# HIVE_BOARD_USB.net
KiCad netlist of a schematic drawn in Altium Designer
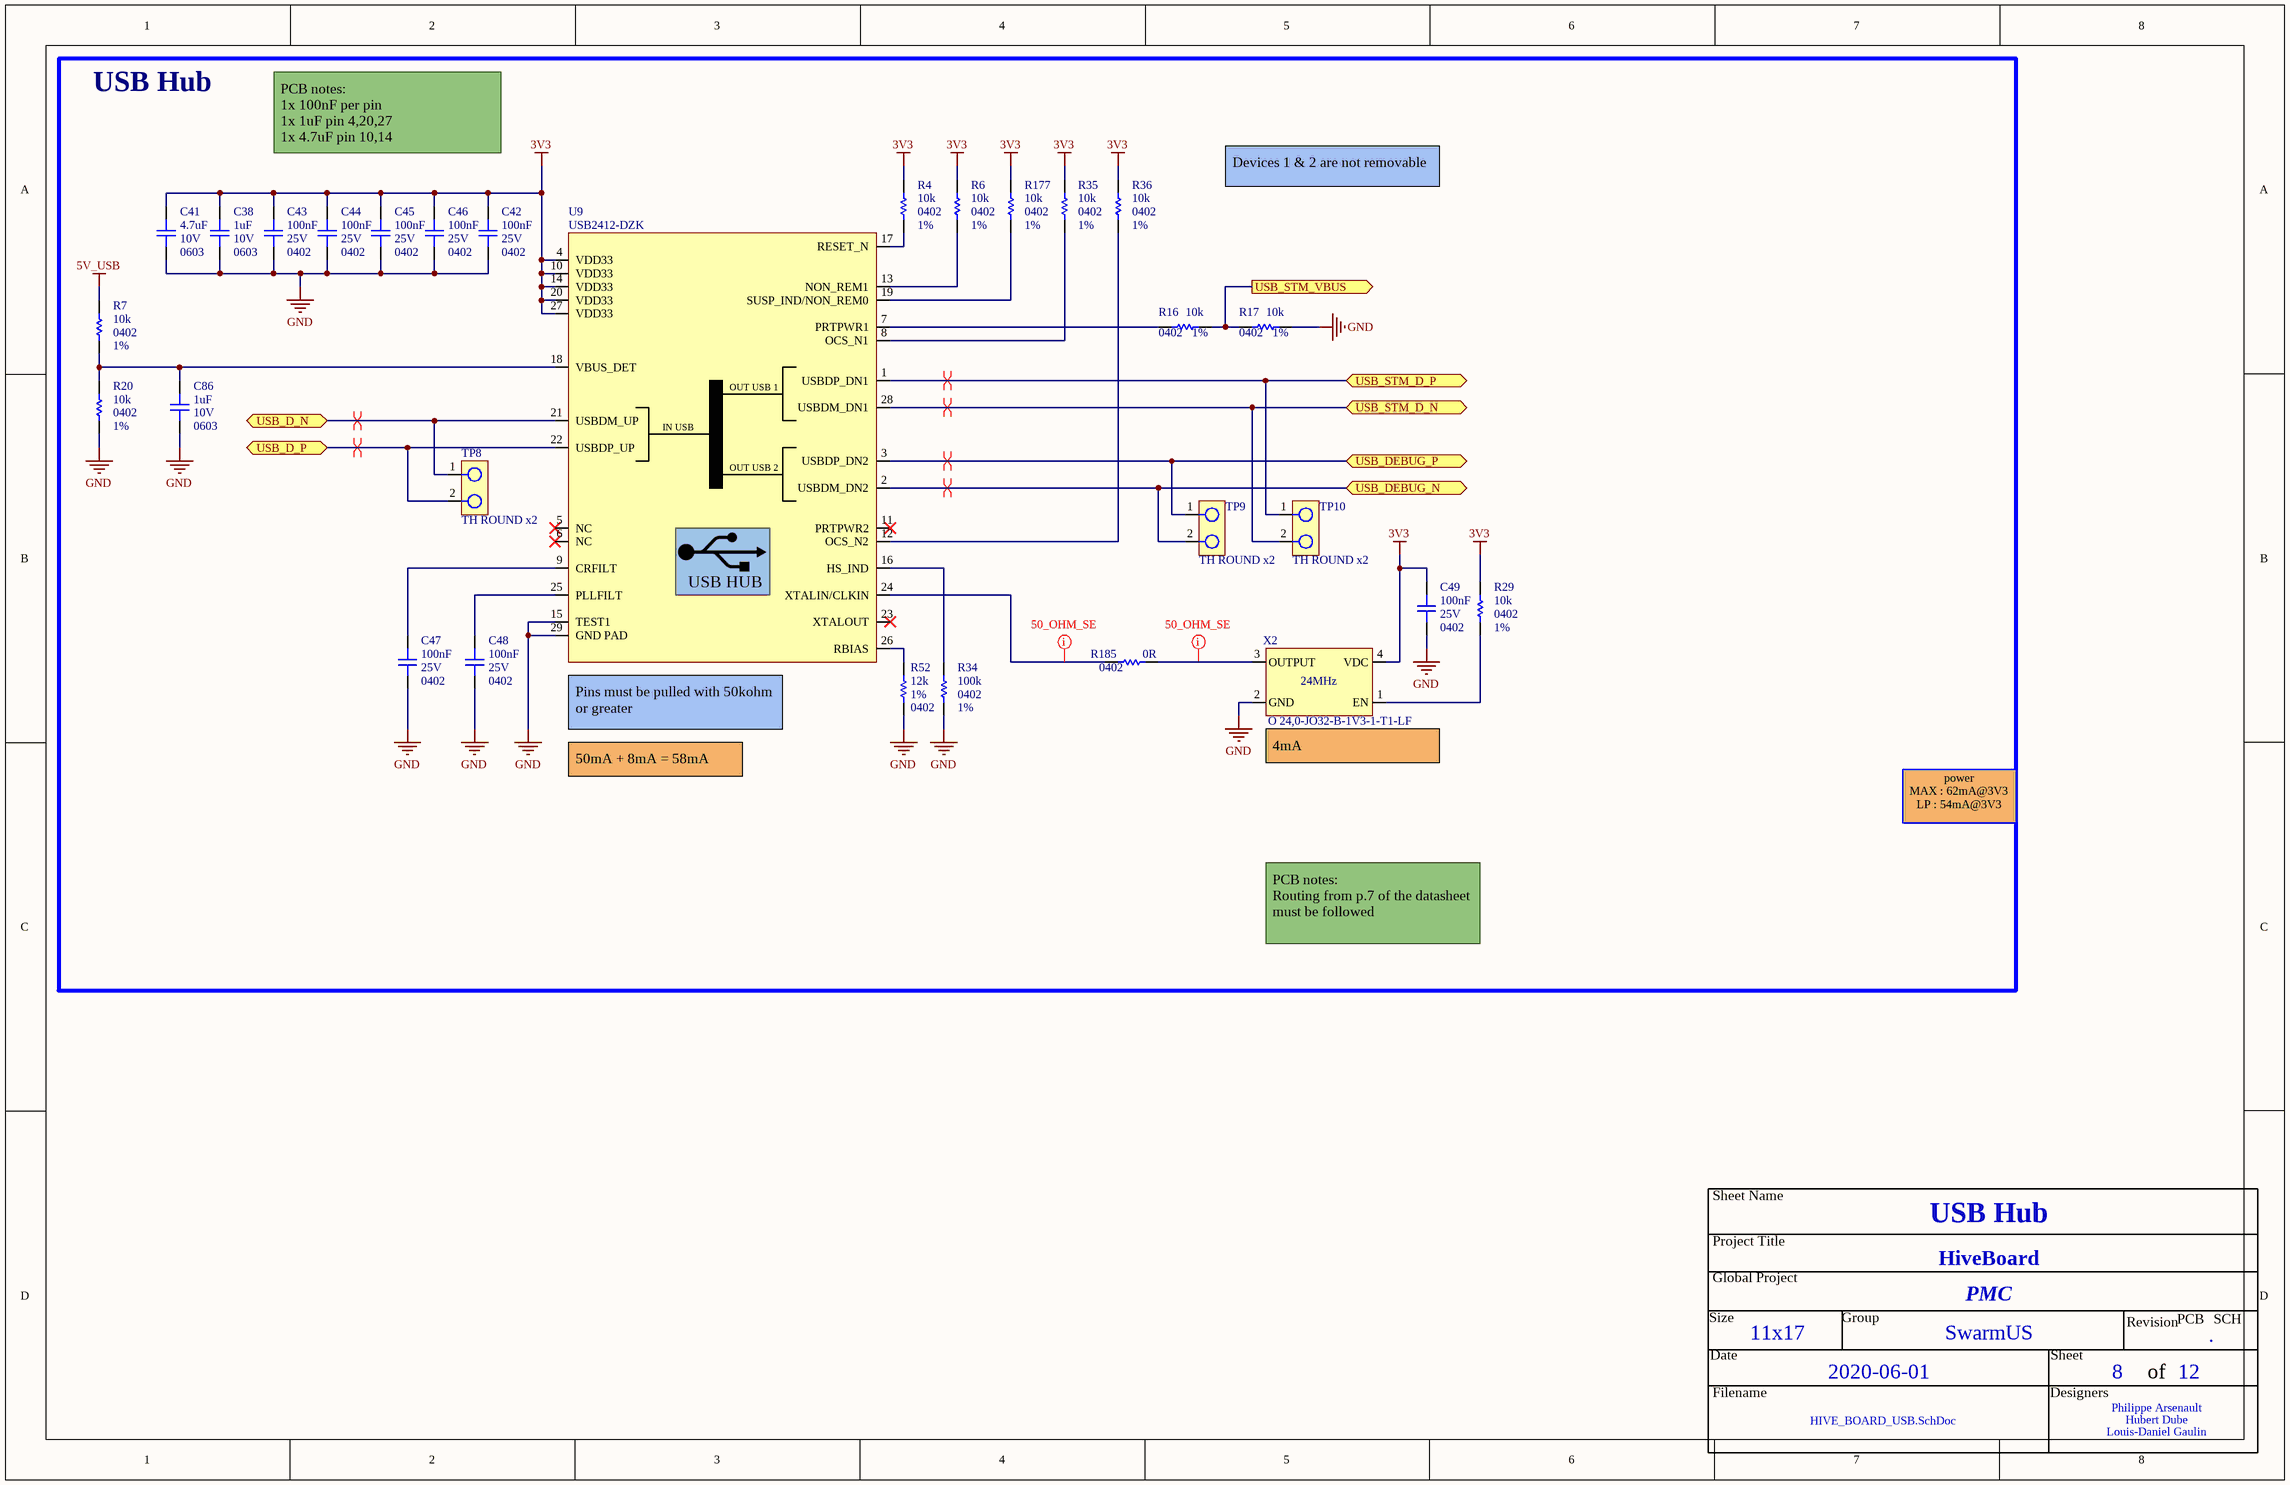
[diagram p0: HIVE_BOARD_USB.SchDoc]

(export (version "E")
  (design (tool "Eeschema 10.0.6"))
  (components
    (comp (ref "C38")
      (value "1uF")
      (footprint "CAP_CER_0603")
      (description "CAP - CER 1uF 10V 10% X5R - 0603")
      (fields
        (field (name "TOLERANCE") "10%")
        (field (name "PACKAGE") "0603")
        (field (name "VOLTAGE RATING") "10V")
        (field (name "Comment") "C0603C105K8PACTU")
        (field (name "CREATEDBY/DATE") "Hubert Dube - 21/07/20")
        (field (name "VERIFIEDBY") "Louis-Daniel Gaulin - 21/07/20")
      )
      (libsource (lib "SWARMUS_LIB") (part "CAP_CER_C0603C105K8PACTU"))
    )
    (comp (ref "C41")
      (value "4.7uF")
      (footprint "CAP_CER_0603")
      (description "4.7µF ±10% 10V Ceramic Capacitor X5R 0603")
      (fields
        (field (name "TOLERANCE") "10%")
        (field (name "PACKAGE") "0603")
        (field (name "VOLTAGE RATING") "10V")
        (field (name "Comment") "CL10A475KP8NNNC")
        (field (name "CREATEDBY/DATE") "Hubert Dube - 25/02/2021")
        (field (name "VERIFIEDBY") "Philippe Arsenault/2021-03-14")
      )
      (libsource (lib "SWARMUS_LIB") (part "CAP_CER_CL10A475KP8NNNC"))
    )
    (comp (ref "C42")
      (value "100nF")
      (footprint "CAP_CER_0402")
      (description "CAP - CER 0.1µF 10% 25V X7R - 0402")
      (fields
        (field (name "TOLERANCE") "10%")
        (field (name "PACKAGE") "0402")
        (field (name "VOLTAGE RATING") "25V")
        (field (name "Comment") "CGA2B3X7R1E104K050BB")
        (field (name "CREATEDBY/DATE") "Nicolas Roy 2018-11-07")
        (field (name "VERIFIEDBY") "Nicolas V. (2019-01-22)")
      )
      (libsource (lib "GRAMS_MASTER_LIB") (part "CAP_CER_CGA2B3X7R1E104K050BB"))
    )
    (comp (ref "C43")
      (value "100nF")
      (footprint "CAP_CER_0402")
      (description "CAP - CER 0.1µF 10% 25V X7R - 0402")
      (fields
        (field (name "TOLERANCE") "10%")
        (field (name "PACKAGE") "0402")
        (field (name "VOLTAGE RATING") "25V")
        (field (name "Comment") "CGA2B3X7R1E104K050BB")
        (field (name "CREATEDBY/DATE") "Nicolas Roy 2018-11-07")
        (field (name "VERIFIEDBY") "Nicolas V. (2019-01-22)")
      )
      (libsource (lib "GRAMS_MASTER_LIB") (part "CAP_CER_CGA2B3X7R1E104K050BB"))
    )
    (comp (ref "C44")
      (value "100nF")
      (footprint "CAP_CER_0402")
      (description "CAP - CER 0.1µF 10% 25V X7R - 0402")
      (fields
        (field (name "TOLERANCE") "10%")
        (field (name "PACKAGE") "0402")
        (field (name "VOLTAGE RATING") "25V")
        (field (name "Comment") "CGA2B3X7R1E104K050BB")
        (field (name "CREATEDBY/DATE") "Nicolas Roy 2018-11-07")
        (field (name "VERIFIEDBY") "Nicolas V. (2019-01-22)")
      )
      (libsource (lib "GRAMS_MASTER_LIB") (part "CAP_CER_CGA2B3X7R1E104K050BB"))
    )
    (comp (ref "C45")
      (value "100nF")
      (footprint "CAP_CER_0402")
      (description "CAP - CER 0.1µF 10% 25V X7R - 0402")
      (fields
        (field (name "TOLERANCE") "10%")
        (field (name "PACKAGE") "0402")
        (field (name "VOLTAGE RATING") "25V")
        (field (name "Comment") "CGA2B3X7R1E104K050BB")
        (field (name "CREATEDBY/DATE") "Nicolas Roy 2018-11-07")
        (field (name "VERIFIEDBY") "Nicolas V. (2019-01-22)")
      )
      (libsource (lib "GRAMS_MASTER_LIB") (part "CAP_CER_CGA2B3X7R1E104K050BB"))
    )
    (comp (ref "C46")
      (value "100nF")
      (footprint "CAP_CER_0402")
      (description "CAP - CER 0.1µF 10% 25V X7R - 0402")
      (fields
        (field (name "TOLERANCE") "10%")
        (field (name "PACKAGE") "0402")
        (field (name "VOLTAGE RATING") "25V")
        (field (name "Comment") "CGA2B3X7R1E104K050BB")
        (field (name "CREATEDBY/DATE") "Nicolas Roy 2018-11-07")
        (field (name "VERIFIEDBY") "Nicolas V. (2019-01-22)")
      )
      (libsource (lib "GRAMS_MASTER_LIB") (part "CAP_CER_CGA2B3X7R1E104K050BB"))
    )
    (comp (ref "C47")
      (value "100nF")
      (footprint "CAP_CER_0402")
      (description "CAP - CER 0.1µF 10% 25V X7R - 0402")
      (fields
        (field (name "TOLERANCE") "10%")
        (field (name "PACKAGE") "0402")
        (field (name "VOLTAGE RATING") "25V")
        (field (name "Comment") "CGA2B3X7R1E104K050BB")
        (field (name "CREATEDBY/DATE") "Nicolas Roy 2018-11-07")
        (field (name "VERIFIEDBY") "Nicolas V. (2019-01-22)")
      )
      (libsource (lib "GRAMS_MASTER_LIB") (part "CAP_CER_CGA2B3X7R1E104K050BB"))
    )
    (comp (ref "C48")
      (value "100nF")
      (footprint "CAP_CER_0402")
      (description "CAP - CER 0.1µF 10% 25V X7R - 0402")
      (fields
        (field (name "TOLERANCE") "10%")
        (field (name "PACKAGE") "0402")
        (field (name "VOLTAGE RATING") "25V")
        (field (name "Comment") "CGA2B3X7R1E104K050BB")
        (field (name "CREATEDBY/DATE") "Nicolas Roy 2018-11-07")
        (field (name "VERIFIEDBY") "Nicolas V. (2019-01-22)")
      )
      (libsource (lib "GRAMS_MASTER_LIB") (part "CAP_CER_CGA2B3X7R1E104K050BB"))
    )
    (comp (ref "C49")
      (value "100nF")
      (footprint "CAP_CER_0402")
      (description "CAP - CER 0.1µF 10% 25V X7R - 0402")
      (fields
        (field (name "TOLERANCE") "10%")
        (field (name "PACKAGE") "0402")
        (field (name "VOLTAGE RATING") "25V")
        (field (name "Comment") "CGA2B3X7R1E104K050BB")
        (field (name "CREATEDBY/DATE") "Nicolas Roy 2018-11-07")
        (field (name "VERIFIEDBY") "Nicolas V. (2019-01-22)")
      )
      (libsource (lib "GRAMS_MASTER_LIB") (part "CAP_CER_CGA2B3X7R1E104K050BB"))
    )
    (comp (ref "C86")
      (value "1uF")
      (footprint "CAP_CER_0603")
      (description "CAP - CER 1uF 10V 10% X5R - 0603")
      (fields
        (field (name "TOLERANCE") "10%")
        (field (name "PACKAGE") "0603")
        (field (name "VOLTAGE RATING") "10V")
        (field (name "Comment") "C0603C105K8PACTU")
        (field (name "CREATEDBY/DATE") "Hubert Dube - 21/07/20")
        (field (name "VERIFIEDBY") "Louis-Daniel Gaulin - 21/07/20")
      )
      (libsource (lib "SWARMUS_LIB") (part "CAP_CER_C0603C105K8PACTU"))
    )
    (comp (ref "R4")
      (value "10k")
      (footprint "RES_0402")
      (description "RES - 10K OHMS 1% 1/16W - 0402")
      (fields
        (field (name "TOLERANCE") "1%")
        (field (name "PACKAGE") "0402")
        (field (name "Comment") "RC0402FR-0710KL")
        (field (name "CREATEDBY/DATE") "Nicolas V. (2018-11-20)")
        (field (name "VERIFIEDBY") "Nicolas V. (2018-11-20)")
      )
      (libsource (lib "GRAMS_MASTER_LIB") (part "RES_RC0402FR-0710KL"))
    )
    (comp (ref "R6")
      (value "10k")
      (footprint "RES_0402")
      (description "RES - 10K OHMS 1% 1/16W - 0402")
      (fields
        (field (name "TOLERANCE") "1%")
        (field (name "PACKAGE") "0402")
        (field (name "Comment") "RC0402FR-0710KL")
        (field (name "CREATEDBY/DATE") "Nicolas V. (2018-11-20)")
        (field (name "VERIFIEDBY") "Nicolas V. (2018-11-20)")
      )
      (libsource (lib "GRAMS_MASTER_LIB") (part "RES_RC0402FR-0710KL"))
    )
    (comp (ref "R7")
      (value "10k")
      (footprint "RES_0402")
      (description "RES - 10K OHMS 1% 1/16W - 0402")
      (fields
        (field (name "TOLERANCE") "1%")
        (field (name "PACKAGE") "0402")
        (field (name "Comment") "RC0402FR-0710KL")
        (field (name "CREATEDBY/DATE") "Nicolas V. (2018-11-20)")
        (field (name "VERIFIEDBY") "Nicolas V. (2018-11-20)")
      )
      (libsource (lib "GRAMS_MASTER_LIB") (part "RES_RC0402FR-0710KL"))
    )
    (comp (ref "R16")
      (value "10k")
      (footprint "RES_0402")
      (description "RES - 10K OHMS 1% 1/16W - 0402")
      (fields
        (field (name "TOLERANCE") "1%")
        (field (name "PACKAGE") "0402")
        (field (name "Comment") "RC0402FR-0710KL")
        (field (name "CREATEDBY/DATE") "Nicolas V. (2018-11-20)")
        (field (name "VERIFIEDBY") "Nicolas V. (2018-11-20)")
      )
      (libsource (lib "GRAMS_MASTER_LIB") (part "RES_RC0402FR-0710KL"))
    )
    (comp (ref "R17")
      (value "10k")
      (footprint "RES_0402")
      (description "RES - 10K OHMS 1% 1/16W - 0402")
      (fields
        (field (name "TOLERANCE") "1%")
        (field (name "PACKAGE") "0402")
        (field (name "Comment") "RC0402FR-0710KL")
        (field (name "CREATEDBY/DATE") "Nicolas V. (2018-11-20)")
        (field (name "VERIFIEDBY") "Nicolas V. (2018-11-20)")
      )
      (libsource (lib "GRAMS_MASTER_LIB") (part "RES_RC0402FR-0710KL"))
    )
    (comp (ref "R20")
      (value "10k")
      (footprint "RES_0402")
      (description "RES - 10K OHMS 1% 1/16W - 0402")
      (fields
        (field (name "TOLERANCE") "1%")
        (field (name "PACKAGE") "0402")
        (field (name "Comment") "RC0402FR-0710KL")
        (field (name "CREATEDBY/DATE") "Nicolas V. (2018-11-20)")
        (field (name "VERIFIEDBY") "Nicolas V. (2018-11-20)")
      )
      (libsource (lib "GRAMS_MASTER_LIB") (part "RES_RC0402FR-0710KL"))
    )
    (comp (ref "R29")
      (value "10k")
      (footprint "RES_0402")
      (description "RES - 10K OHMS 1% 1/16W - 0402")
      (fields
        (field (name "TOLERANCE") "1%")
        (field (name "PACKAGE") "0402")
        (field (name "Comment") "RC0402FR-0710KL")
        (field (name "CREATEDBY/DATE") "Nicolas V. (2018-11-20)")
        (field (name "VERIFIEDBY") "Nicolas V. (2018-11-20)")
      )
      (libsource (lib "GRAMS_MASTER_LIB") (part "RES_RC0402FR-0710KL"))
    )
    (comp (ref "R34")
      (value "100k")
      (footprint "RES_0402")
      (description "RES - 100K 1% 1/16W - 0402")
      (fields
        (field (name "TOLERANCE") "1%")
        (field (name "PACKAGE") "0402")
        (field (name "Comment") "RC0402FR-07100KL")
        (field (name "CREATEDBY/DATE") "Keven Deslandes 2018-10-19")
        (field (name "VERIFIEDBY") "Caroline Paulin - 18/12/2018")
      )
      (libsource (lib "GRAMS_MASTER_LIB") (part "RES_RC0402FR-07100KL"))
    )
    (comp (ref "R35")
      (value "10k")
      (footprint "RES_0402")
      (description "RES - 10K OHMS 1% 1/16W - 0402")
      (fields
        (field (name "TOLERANCE") "1%")
        (field (name "PACKAGE") "0402")
        (field (name "Comment") "RC0402FR-0710KL")
        (field (name "CREATEDBY/DATE") "Nicolas V. (2018-11-20)")
        (field (name "VERIFIEDBY") "Nicolas V. (2018-11-20)")
      )
      (libsource (lib "GRAMS_MASTER_LIB") (part "RES_RC0402FR-0710KL"))
    )
    (comp (ref "R36")
      (value "10k")
      (footprint "RES_0402")
      (description "RES - 10K OHMS 1% 1/16W - 0402")
      (fields
        (field (name "TOLERANCE") "1%")
        (field (name "PACKAGE") "0402")
        (field (name "Comment") "RC0402FR-0710KL")
        (field (name "CREATEDBY/DATE") "Nicolas V. (2018-11-20)")
        (field (name "VERIFIEDBY") "Nicolas V. (2018-11-20)")
      )
      (libsource (lib "GRAMS_MASTER_LIB") (part "RES_RC0402FR-0710KL"))
    )
    (comp (ref "R52")
      (value "12k")
      (footprint "RES_0402")
      (description "RES - 12k Ohms ±1% 0.063W, 1/16W Chip Resistor 0402 (1005 Metric) Moisture Resistant Thick Film")
      (fields
        (field (name "TOLERANCE") "1%")
        (field (name "PACKAGE") "0402")
        (field (name "Comment") "RC0402FR-0712KL")
        (field (name "CREATEDBY/DATE") "Philippe Arsenault/2021-03-11")
        (field (name "VERIFIEDBY") "Hubert Dube - 19/03/2021")
      )
      (libsource (lib "SWARMUS_LIB") (part "RES_RC0402FR-0712KL"))
    )
    (comp (ref "R177")
      (value "10k")
      (footprint "RES_0402")
      (description "RES - 10K OHMS 1% 1/16W - 0402")
      (fields
        (field (name "TOLERANCE") "1%")
        (field (name "PACKAGE") "0402")
        (field (name "Comment") "RC0402FR-0710KL")
        (field (name "CREATEDBY/DATE") "Nicolas V. (2018-11-20)")
        (field (name "VERIFIEDBY") "Nicolas V. (2018-11-20)")
      )
      (libsource (lib "GRAMS_MASTER_LIB") (part "RES_RC0402FR-0710KL"))
    )
    (comp (ref "R185")
      (value "0R")
      (footprint "RES_0402")
      (description "RES - 0R 1/16W 1A  - 0402")
      (fields
        (field (name "PACKAGE") "0402")
        (field (name "Comment") "RC0402FR-070RL")
        (field (name "CREATEDBY/DATE") "Keven Deslandes 2018-09-12")
        (field (name "VERIFIEDBY") "Caroline Paulin - 27 fév 2019")
      )
      (libsource (lib "GRAMS_MASTER_LIB") (part "RES_RC0402FR-070RL"))
    )
    (comp (ref "TP8")
      (value "TH ROUND x2")
      (footprint "TPO_TH_ROUND_0.7mm_DOUBLE")
      (description "TPO - TH round 0.7mm double - 2-SMD")
      (fields
        (field (name "CREATEDBY/DATE") "Philippe Arsenault / 20-04-2021")
        (field (name "VERIFIEDBY") "Louis-Daniel Gaulin / 29-04-2021")
      )
      (libsource (lib "SWARMUS_LIB") (part "TPO_TH_ROUND_0.7mm_DOUBLE"))
    )
    (comp (ref "TP9")
      (value "TH ROUND x2")
      (footprint "TPO_TH_ROUND_0.7mm_DOUBLE")
      (description "TPO - TH round 0.7mm double - 2-SMD")
      (fields
        (field (name "CREATEDBY/DATE") "Philippe Arsenault / 20-04-2021")
        (field (name "VERIFIEDBY") "Louis-Daniel Gaulin / 29-04-2021")
      )
      (libsource (lib "SWARMUS_LIB") (part "TPO_TH_ROUND_0.7mm_DOUBLE"))
    )
    (comp (ref "TP10")
      (value "TH ROUND x2")
      (footprint "TPO_TH_ROUND_0.7mm_DOUBLE")
      (description "TPO - TH round 0.7mm double - 2-SMD")
      (fields
        (field (name "CREATEDBY/DATE") "Philippe Arsenault / 20-04-2021")
        (field (name "VERIFIEDBY") "Louis-Daniel Gaulin / 29-04-2021")
      )
      (libsource (lib "SWARMUS_LIB") (part "TPO_TH_ROUND_0.7mm_DOUBLE"))
    )
    (comp (ref "U9")
      (value "USB2412-DZK")
      (footprint "USB_USB2412-DZK")
      (description "USB Hub Controller USB 2.0 USB Interface 28-QFN")
      (fields
        (field (name "VERIFIEDBY") "Philippe Arsenault/2021-03-14")
        (field (name "CREATEDBY/DATE") "Hubert Dube -  12/02/2021")
      )
      (libsource (lib "SWARMUS_LIB") (part "USB_USB2412-DZK"))
    )
    (comp (ref "X2")
      (value "O 24,0-JO32-B-1V3-1-T1-LF")
      (footprint "OSC_O 24,0-JO32-B-1V3-1-T1-LF")
      (description "OSC - 24MHz XO (Standard) LVCMOS Oscillator 1.8V ~ 3.3V Enable/Disable 4-SMD, No Lead")
      (fields
        (field (name "TOLERANCE") "±50ppm")
        (field (name "CREATEDBY/DATE") "Louis-Daniel Gaulin / 13-04-2021")
        (field (name "VERIFIEDBY") "Philippe Arsenault/2021-04-14")
      )
      (libsource (lib "SWARMUS_LIB") (part "OSC_O 24,0-JO32-B-1V3-1-T1-LF"))
    )
  )
  (nets
    (net (code "1") (name "/USB_DEBUG_N") (class "Default")
      (node (ref "TP9") (pin "2") (pinfunction "2_2") (pintype "passive"))
      (node (ref "U9") (pin "2") (pinfunction "USBDM_DN2_2") (pintype "passive"))
    )
    (net (code "2") (name "/USB_DEBUG_P") (class "Default")
      (node (ref "TP9") (pin "1") (pinfunction "1_1") (pintype "passive"))
      (node (ref "U9") (pin "3") (pinfunction "USBDP_DN2_3") (pintype "passive"))
    )
    (net (code "3") (name "/USB_D_N") (class "Default")
      (node (ref "TP8") (pin "1") (pinfunction "1_1") (pintype "passive"))
      (node (ref "U9") (pin "21") (pinfunction "USBDM_UP_21") (pintype "passive"))
    )
    (net (code "4") (name "/USB_D_P") (class "Default")
      (node (ref "TP8") (pin "2") (pinfunction "2_2") (pintype "passive"))
      (node (ref "U9") (pin "22") (pinfunction "USBDP_UP_22") (pintype "passive"))
    )
    (net (code "5") (name "/USB_STM_D_N") (class "Default")
      (node (ref "TP10") (pin "2") (pinfunction "2_2") (pintype "passive"))
      (node (ref "U9") (pin "28") (pinfunction "USBDM_DN1_28") (pintype "passive"))
    )
    (net (code "6") (name "/USB_STM_D_P") (class "Default")
      (node (ref "TP10") (pin "1") (pinfunction "1_1") (pintype "passive"))
      (node (ref "U9") (pin "1") (pinfunction "USBDP_DN1_1") (pintype "passive"))
    )
    (net (code "7") (name "/USB_STM_VBUS") (class "Default")
      (node (ref "R16") (pin "2") (pinfunction "2_2") (pintype "passive"))
      (node (ref "R17") (pin "1") (pinfunction "1_1") (pintype "passive"))
    )
    (net (code "8") (name "3V3") (class "Default")
      (node (ref "C38") (pin "1") (pinfunction "1_1") (pintype "passive"))
      (node (ref "C41") (pin "2") (pinfunction "2_2") (pintype "passive"))
      (node (ref "C42") (pin "2") (pinfunction "2_2") (pintype "passive"))
      (node (ref "C43") (pin "2") (pinfunction "2_2") (pintype "passive"))
      (node (ref "C44") (pin "2") (pinfunction "2_2") (pintype "passive"))
      (node (ref "C45") (pin "2") (pinfunction "2_2") (pintype "passive"))
      (node (ref "C46") (pin "2") (pinfunction "2_2") (pintype "passive"))
      (node (ref "C49") (pin "2") (pinfunction "2_2") (pintype "passive"))
      (node (ref "R177") (pin "1") (pinfunction "1_1") (pintype "passive"))
      (node (ref "R29") (pin "1") (pinfunction "1_1") (pintype "passive"))
      (node (ref "R35") (pin "1") (pinfunction "1_1") (pintype "passive"))
      (node (ref "R36") (pin "1") (pinfunction "1_1") (pintype "passive"))
      (node (ref "R4") (pin "1") (pinfunction "1_1") (pintype "passive"))
      (node (ref "R6") (pin "1") (pinfunction "1_1") (pintype "passive"))
      (node (ref "U9") (pin "10") (pinfunction "VDD33_10") (pintype "passive"))
      (node (ref "U9") (pin "14") (pinfunction "VDD33_14") (pintype "passive"))
      (node (ref "U9") (pin "20") (pinfunction "VDD33_20") (pintype "passive"))
      (node (ref "U9") (pin "27") (pinfunction "VDD33_27") (pintype "passive"))
      (node (ref "U9") (pin "4") (pinfunction "VDD33_4") (pintype "passive"))
      (node (ref "X2") (pin "4") (pinfunction "VDC_4") (pintype "passive"))
    )
    (net (code "9") (name "5V_USB") (class "Default")
      (node (ref "R7") (pin "1") (pinfunction "1_1") (pintype "passive"))
    )
    (net (code "10") (name "GND") (class "Default")
      (node (ref "C38") (pin "2") (pinfunction "2_2") (pintype "passive"))
      (node (ref "C41") (pin "1") (pinfunction "1_1") (pintype "passive"))
      (node (ref "C42") (pin "1") (pinfunction "1_1") (pintype "passive"))
      (node (ref "C43") (pin "1") (pinfunction "1_1") (pintype "passive"))
      (node (ref "C44") (pin "1") (pinfunction "1_1") (pintype "passive"))
      (node (ref "C45") (pin "1") (pinfunction "1_1") (pintype "passive"))
      (node (ref "C46") (pin "1") (pinfunction "1_1") (pintype "passive"))
      (node (ref "C47") (pin "1") (pinfunction "1_1") (pintype "passive"))
      (node (ref "C48") (pin "1") (pinfunction "1_1") (pintype "passive"))
      (node (ref "C49") (pin "1") (pinfunction "1_1") (pintype "passive"))
      (node (ref "C86") (pin "2") (pinfunction "2_2") (pintype "passive"))
      (node (ref "R17") (pin "2") (pinfunction "2_2") (pintype "passive"))
      (node (ref "R20") (pin "2") (pinfunction "2_2") (pintype "passive"))
      (node (ref "R34") (pin "2") (pinfunction "2_2") (pintype "passive"))
      (node (ref "R52") (pin "1") (pinfunction "1_1") (pintype "passive"))
      (node (ref "U9") (pin "15") (pinfunction "TEST1_15") (pintype "passive"))
      (node (ref "U9") (pin "29") (pinfunction "GND_PAD_29") (pintype "passive"))
      (node (ref "X2") (pin "2") (pinfunction "GND_2") (pintype "passive"))
    )
    (net (code "11") (name "Net-(U9-CRFILT)") (class "Default")
      (node (ref "C47") (pin "2") (pinfunction "2_2") (pintype "passive"))
      (node (ref "U9") (pin "9") (pinfunction "CRFILT_9") (pintype "passive"))
    )
    (net (code "12") (name "Net-(U9-HS_IND)") (class "Default")
      (node (ref "R34") (pin "1") (pinfunction "1_1") (pintype "passive"))
      (node (ref "U9") (pin "16") (pinfunction "HS_IND_16") (pintype "passive"))
    )
    (net (code "13") (name "Net-(U9-NON_REM1)") (class "Default")
      (node (ref "R6") (pin "2") (pinfunction "2_2") (pintype "passive"))
      (node (ref "U9") (pin "13") (pinfunction "NON_REM1_13") (pintype "passive"))
    )
    (net (code "14") (name "Net-(U9-OCS_N1)") (class "Default")
      (node (ref "R35") (pin "2") (pinfunction "2_2") (pintype "passive"))
      (node (ref "U9") (pin "8") (pinfunction "OCS_N1_8") (pintype "passive"))
    )
    (net (code "15") (name "Net-(U9-OCS_N2)") (class "Default")
      (node (ref "R36") (pin "2") (pinfunction "2_2") (pintype "passive"))
      (node (ref "U9") (pin "12") (pinfunction "OCS_N2_12") (pintype "passive"))
    )
    (net (code "16") (name "Net-(U9-PLLFILT)") (class "Default")
      (node (ref "C48") (pin "2") (pinfunction "2_2") (pintype "passive"))
      (node (ref "U9") (pin "25") (pinfunction "PLLFILT_25") (pintype "passive"))
    )
    (net (code "17") (name "Net-(U9-PRTPWR1)") (class "Default")
      (node (ref "R16") (pin "1") (pinfunction "1_1") (pintype "passive"))
      (node (ref "U9") (pin "7") (pinfunction "PRTPWR1_7") (pintype "passive"))
    )
    (net (code "18") (name "Net-(U9-RBIAS)") (class "Default")
      (node (ref "R52") (pin "2") (pinfunction "2_2") (pintype "passive"))
      (node (ref "U9") (pin "26") (pinfunction "RBIAS_26") (pintype "passive"))
    )
    (net (code "19") (name "Net-(U9-RESET_N)") (class "Default")
      (node (ref "R4") (pin "2") (pinfunction "2_2") (pintype "passive"))
      (node (ref "U9") (pin "17") (pinfunction "RESET_N_17") (pintype "passive"))
    )
    (net (code "20") (name "Net-(U9-SUSP_IND{slash}NON_REM0)") (class "Default")
      (node (ref "R177") (pin "2") (pinfunction "2_2") (pintype "passive"))
      (node (ref "U9") (pin "19") (pinfunction "SUSP_IND/NON_REM0_19") (pintype "passive"))
    )
    (net (code "21") (name "Net-(U9-VBUS_DET)") (class "Default")
      (node (ref "C86") (pin "1") (pinfunction "1_1") (pintype "passive"))
      (node (ref "R20") (pin "1") (pinfunction "1_1") (pintype "passive"))
      (node (ref "R7") (pin "2") (pinfunction "2_2") (pintype "passive"))
      (node (ref "U9") (pin "18") (pinfunction "VBUS_DET_18") (pintype "passive"))
    )
    (net (code "22") (name "Net-(U9-XTALIN{slash}CLKIN)") (class "Default")
      (node (ref "R185") (pin "2") (pinfunction "2_2") (pintype "passive"))
      (node (ref "U9") (pin "24") (pinfunction "XTALIN/CLKIN_24") (pintype "passive"))
    )
    (net (code "23") (name "Net-(X2-EN)") (class "Default")
      (node (ref "R29") (pin "2") (pinfunction "2_2") (pintype "passive"))
      (node (ref "X2") (pin "1") (pinfunction "EN_1") (pintype "passive"))
    )
    (net (code "24") (name "Net-(X2-OUTPUT)") (class "Default")
      (node (ref "R185") (pin "1") (pinfunction "1_1") (pintype "passive"))
      (node (ref "X2") (pin "3") (pinfunction "OUTPUT_3") (pintype "passive"))
    )
    (net (code "25") (name "unconnected-(U9-NC-Pad5)") (class "Default")
      (node (ref "U9") (pin "5") (pinfunction "NC_5") (pintype "passive+no_connect"))
    )
    (net (code "26") (name "unconnected-(U9-NC-Pad6)") (class "Default")
      (node (ref "U9") (pin "6") (pinfunction "NC_6") (pintype "passive+no_connect"))
    )
    (net (code "27") (name "unconnected-(U9-PRTPWR2-Pad11)") (class "Default")
      (node (ref "U9") (pin "11") (pinfunction "PRTPWR2_11") (pintype "passive+no_connect"))
    )
    (net (code "28") (name "unconnected-(U9-XTALOUT-Pad23)") (class "Default")
      (node (ref "U9") (pin "23") (pinfunction "XTALOUT_23") (pintype "passive+no_connect"))
    )
  )
)
